# Sensor.net
KiCad netlist of a schematic drawn in Altium Designer
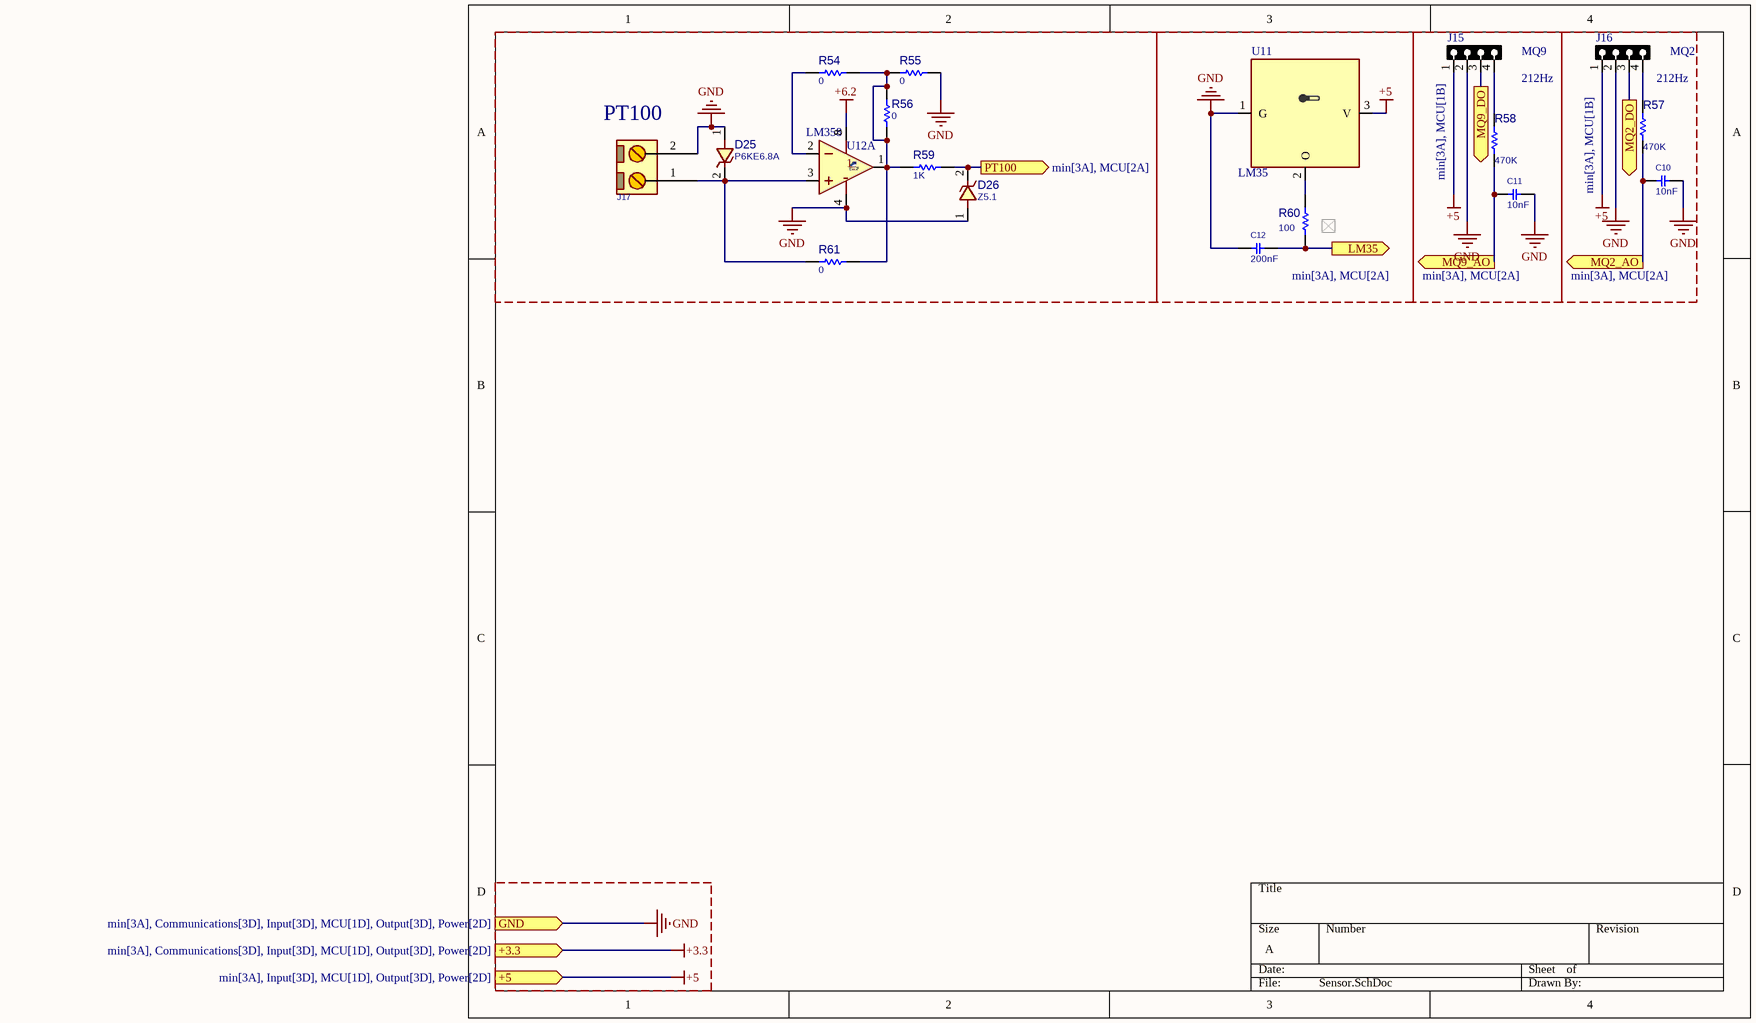
[diagram p0: Sensor.SchDoc]

(export (version "E")
  (design (tool "Eeschema 10.0.6"))
  (components
    (comp (ref "C10")
      (value "10nF")
      (footprint "C1206")
      (description "CAP, MLCC")
      (fields (field (name "MANF_P#") "MANF_PART#") (field (name "MANF") "Murata"))
      (libsource (lib "passive_smd") (part "CAP_SMD_MLCC"))
    )
    (comp (ref "C11")
      (value "10nF")
      (footprint "C1206")
      (description "CAP, MLCC")
      (fields (field (name "MANF_P#") "MANF_PART#") (field (name "MANF") "Murata"))
      (libsource (lib "passive_smd") (part "CAP_SMD_MLCC"))
    )
    (comp (ref "C12")
      (value "200nF")
      (footprint "C1206")
      (description "CAP, MLCC")
      (fields (field (name "MANF_P#") "MANF_PART#") (field (name "MANF") "Murata"))
      (libsource (lib "passive_smd") (part "CAP_SMD_MLCC"))
    )
    (comp (ref "D25")
      (value "P6KE6.8A")
      (footprint "D_AX04_DO41")
      (description "DIODE, ZENER, 0.2W, 15V")
      (fields (field (name "MANF") "Diodes") (field (name "MANF_P#") "ZENER15V"))
      (libsource (lib "diode") (part "DIODE_THD_ZENER"))
    )
    (comp (ref "D26")
      (value "Z5.1")
      (footprint "D_AX04_DO41")
      (description "DIODE, ZENER, 0.2W, 15V")
      (fields (field (name "MANF") "Diodes") (field (name "MANF_P#") "ZENER15V"))
      (libsource (lib "diode") (part "DIODE_THD_ZENER"))
    )
    (comp (ref "J15")
      (value "MQ9")
      (footprint "HDR_F_1X4")
      (description "CONN, HEADER, Female, pitch: 2.54mm, 4POS")
      (libsource (lib "conn_header_2.54mm_st") (part "HDR_F_1X4"))
    )
    (comp (ref "J16")
      (value "MQ2")
      (footprint "HDR_F_1X4")
      (description "CONN, HEADER, Female, pitch: 2.54mm, 4POS")
      (libsource (lib "conn_header_2.54mm_st") (part "HDR_F_1X4"))
    )
    (comp (ref "J17")
      (value "CONN_GMSTB2")
      (footprint "GMSTB762_2")
      (description "CONN, PHOENIX GMSTB, 7.62mm pitch")
      (fields (field (name "MANF_P#") "GMSTB 2,5/2-G-7,62"))
      (libsource (lib "conn_terminalB") (part "CONN_GMSTB762_2"))
    )
    (comp (ref "R54")
      (value "0")
      (footprint "R1206")
      (description "RESISTOR, SMD")
      (libsource (lib "passive_smd") (part "RES_SMD"))
    )
    (comp (ref "R55")
      (value "0")
      (footprint "R1206")
      (description "RESISTOR, SMD")
      (libsource (lib "passive_smd") (part "RES_SMD"))
    )
    (comp (ref "R56")
      (value "0")
      (footprint "R1206")
      (description "RESISTOR, SMD")
      (libsource (lib "passive_smd") (part "RES_SMD"))
    )
    (comp (ref "R57")
      (value "470K")
      (footprint "R1206")
      (description "RESISTOR, SMD")
      (libsource (lib "passive_smd") (part "RES_SMD"))
    )
    (comp (ref "R58")
      (value "470K")
      (footprint "R1206")
      (description "RESISTOR, SMD")
      (libsource (lib "passive_smd") (part "RES_SMD"))
    )
    (comp (ref "R59")
      (value "1K")
      (footprint "R1206")
      (description "RESISTOR, SMD")
      (libsource (lib "passive_smd") (part "RES_SMD"))
    )
    (comp (ref "R60")
      (value "100")
      (footprint "R1206")
      (description "RESISTOR, SMD")
      (libsource (lib "passive_smd") (part "RES_SMD"))
    )
    (comp (ref "R61")
      (value "0")
      (footprint "R1206")
      (description "RESISTOR, SMD")
      (libsource (lib "passive_smd") (part "RES_SMD"))
    )
    (comp (ref "U11")
      (value "LM35")
      (footprint "TO92_3")
      (description "SENSOR, TEMP, ANALOG, -55~150oC, 4~20Vcc, Out 0mV + 10mV/oC")
      (fields (field (name "MANF_P#") "LM35CZ, LM35CAZ or LM35DZ") (field (name "MANF") "TI"))
      (libsource (lib "sensor_temp&humidity") (part "TMP_LM35_TO92"))
    )
    (comp (ref "U12")
      (value "LM358")
      (footprint "DIP_8")
      (description "AMP, Dual, Low-Power")
      (fields (field (name "MANF") "Texas Instruments, Fairchild") (field (name "MANF_P#") "LM358AN"))
      (libsource (lib "amp") (part "LM358_DIP8"))
    )
  )
  (nets
    (net (code "2") (name "+5") (class "Default")
      (node (ref "J15") (pin "1") (pinfunction "1_1") (pintype "passive"))
      (node (ref "J16") (pin "1") (pinfunction "1_1") (pintype "passive"))
      (node (ref "U11") (pin "3") (pinfunction "V_3") (pintype "passive"))
    )
    (net (code "3") (name "+6.2") (class "Default")
      (node (ref "U12") (pin "8") (pinfunction "V+_8") (pintype "passive"))
    )
    (net (code "4") (name "/LM35") (class "Default")
      (node (ref "C12") (pin "2") (pinfunction "2_2") (pintype "passive"))
      (node (ref "R60") (pin "1") (pinfunction "1_1") (pintype "passive"))
    )
    (net (code "5") (name "/MQ2_AO") (class "Default")
      (node (ref "C10") (pin "1") (pinfunction "1_1") (pintype "passive"))
      (node (ref "R57") (pin "1") (pinfunction "1_1") (pintype "passive"))
    )
    (net (code "6") (name "/MQ2_DO") (class "Default")
      (node (ref "J16") (pin "3") (pinfunction "3_3") (pintype "passive"))
    )
    (net (code "7") (name "/MQ9_AO") (class "Default")
      (node (ref "C11") (pin "1") (pinfunction "1_1") (pintype "passive"))
      (node (ref "R58") (pin "1") (pinfunction "1_1") (pintype "passive"))
    )
    (net (code "8") (name "/MQ9_DO") (class "Default")
      (node (ref "J15") (pin "3") (pinfunction "3_3") (pintype "passive"))
    )
    (net (code "9") (name "/PT100") (class "Default")
      (node (ref "D26") (pin "2") (pinfunction "2_2") (pintype "passive"))
      (node (ref "R59") (pin "2") (pinfunction "2_2") (pintype "passive"))
    )
    (net (code "10") (name "GND") (class "Default")
      (node (ref "C10") (pin "2") (pinfunction "2_2") (pintype "passive"))
      (node (ref "C11") (pin "2") (pinfunction "2_2") (pintype "passive"))
      (node (ref "C12") (pin "1") (pinfunction "1_1") (pintype "passive"))
      (node (ref "D25") (pin "1") (pinfunction "1_1") (pintype "passive"))
      (node (ref "D26") (pin "1") (pinfunction "1_1") (pintype "passive"))
      (node (ref "J15") (pin "2") (pinfunction "2_2") (pintype "passive"))
      (node (ref "J16") (pin "2") (pinfunction "2_2") (pintype "passive"))
      (node (ref "J17") (pin "2") (pinfunction "2_2") (pintype "passive"))
      (node (ref "R55") (pin "1") (pinfunction "1_1") (pintype "passive"))
      (node (ref "U11") (pin "1") (pinfunction "G_1") (pintype "passive"))
      (node (ref "U12") (pin "4") (pinfunction "V-_4") (pintype "passive"))
    )
    (net (code "11") (name "Net-(J15-Pad4)") (class "Default")
      (node (ref "J15") (pin "4") (pinfunction "4_4") (pintype "passive"))
      (node (ref "R58") (pin "2") (pinfunction "2_2") (pintype "passive"))
    )
    (net (code "12") (name "Net-(J16-Pad4)") (class "Default")
      (node (ref "J16") (pin "4") (pinfunction "4_4") (pintype "passive"))
      (node (ref "R57") (pin "2") (pinfunction "2_2") (pintype "passive"))
    )
    (net (code "13") (name "Net-(U11-O)") (class "Default")
      (node (ref "R60") (pin "2") (pinfunction "2_2") (pintype "passive"))
      (node (ref "U11") (pin "2") (pinfunction "O_2") (pintype "passive"))
    )
    (net (code "14") (name "Net-(U12A-IN+)") (class "Default")
      (node (ref "D25") (pin "2") (pinfunction "2_2") (pintype "passive"))
      (node (ref "J17") (pin "1") (pinfunction "1_1") (pintype "passive"))
      (node (ref "R61") (pin "2") (pinfunction "2_2") (pintype "passive"))
      (node (ref "U12") (pin "3") (pinfunction "IN+_3") (pintype "passive"))
    )
    (net (code "15") (name "Net-(U12A-IN-)") (class "Default")
      (node (ref "R54") (pin "2") (pinfunction "2_2") (pintype "passive"))
      (node (ref "U12") (pin "2") (pinfunction "IN-_2") (pintype "passive"))
    )
    (net (code "16") (name "Net-(U12A-OUT)") (class "Default")
      (node (ref "R54") (pin "1") (pinfunction "1_1") (pintype "passive"))
      (node (ref "R55") (pin "2") (pinfunction "2_2") (pintype "passive"))
      (node (ref "R56") (pin "1") (pinfunction "1_1") (pintype "passive"))
      (node (ref "R56") (pin "2") (pinfunction "2_2") (pintype "passive"))
      (node (ref "R59") (pin "1") (pinfunction "1_1") (pintype "passive"))
      (node (ref "R61") (pin "1") (pinfunction "1_1") (pintype "passive"))
      (node (ref "U12") (pin "1") (pinfunction "OUT_1") (pintype "passive"))
    )
  )
)
